# FLEXQCMV1_4.net
KiCad netlist of a schematic drawn in EAGLE
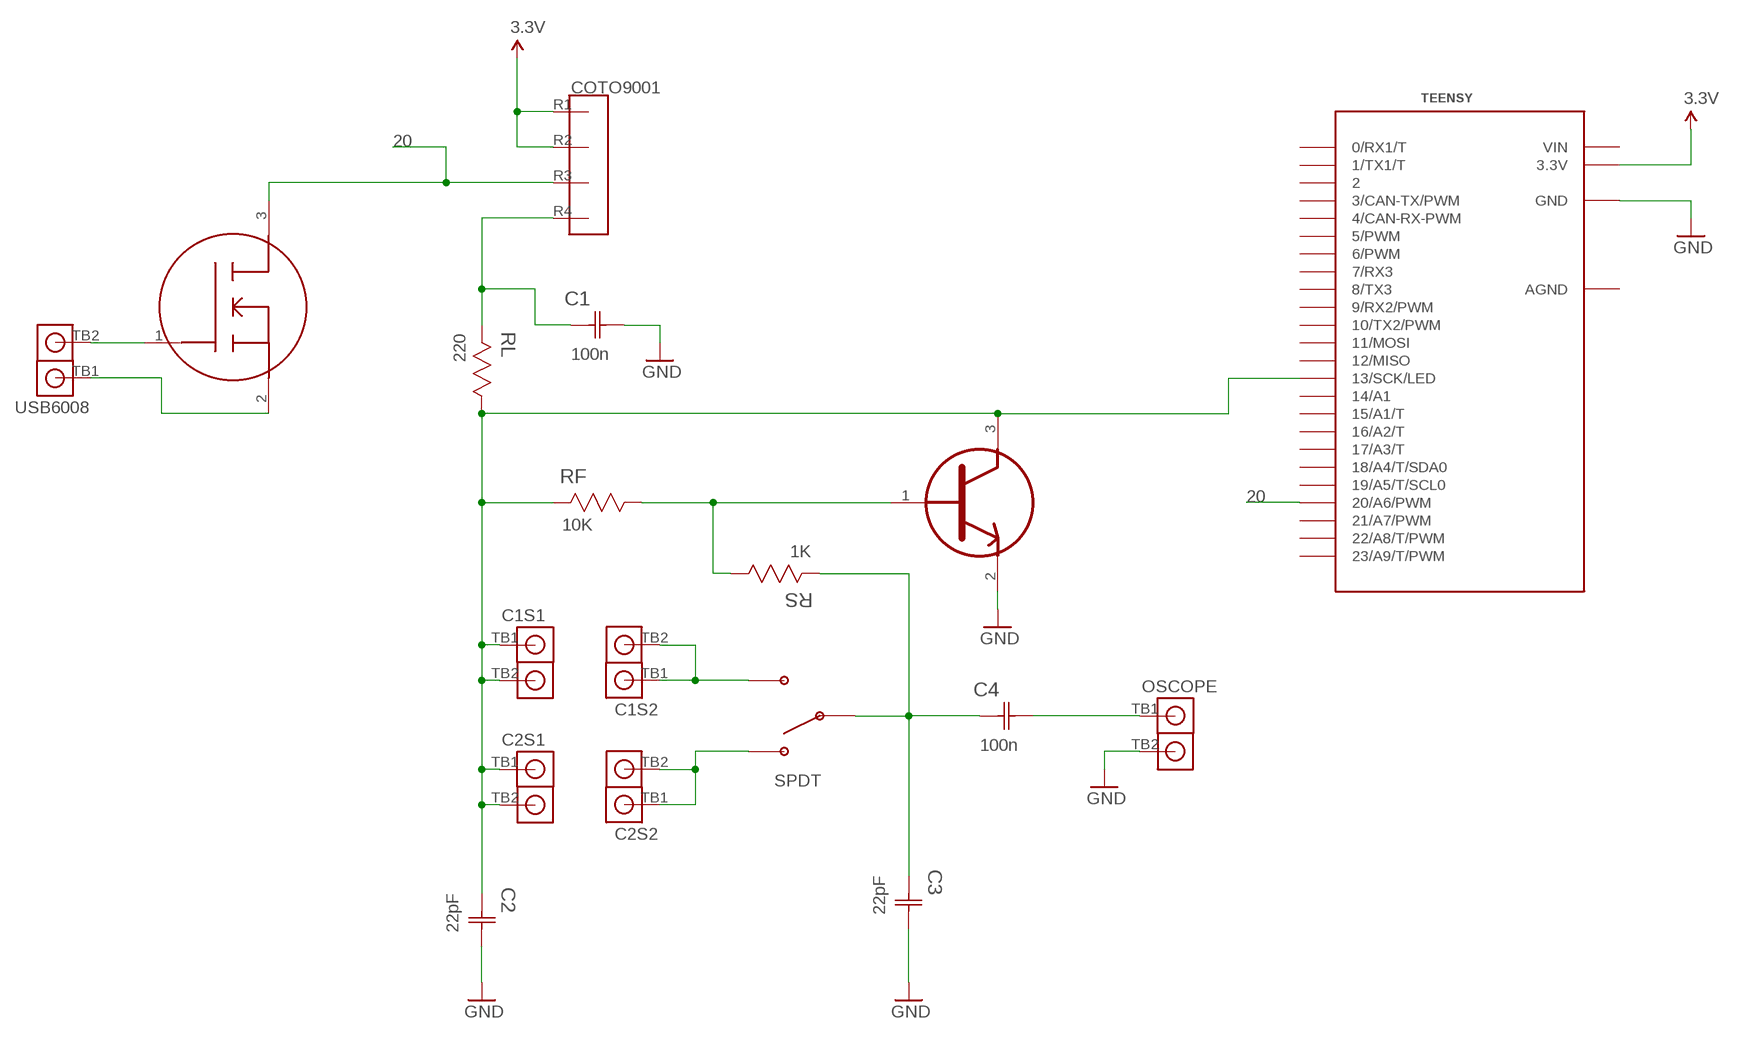
[diagram p0: schematic, sheet 1]

(export (version "E")
  (design (tool "Eeschema 10.0.6"))
  (components
    (comp (ref "C1")
      (value "100n")
      (footprint "eagle-import:CAPC3216X88N")
      (fields (field (name "MPN") "C1206C104K1RACTU") (field (name "TOLERANCE") "±10%"))
      (libsource (lib "eagle-import") (part "C1206C104K1RACTU"))
    )
    (comp (ref "C1S1")
      (value "TERMBLOCKX2")
      (footprint "eagle-import:TERMBLOCKX2")
      (libsource (lib "eagle-import") (part "TERMBLOCKX2"))
    )
    (comp (ref "C1S2")
      (value "TERMBLOCKX2")
      (footprint "eagle-import:TERMBLOCKX2")
      (libsource (lib "eagle-import") (part "TERMBLOCKX2"))
    )
    (comp (ref "C2")
      (value "22pF")
      (footprint "eagle-import:CAPC3216X88N")
      (fields (field (name "MPN") "C1206C220J5GACTU") (field (name "TOLERANCE") "±5%"))
      (libsource (lib "eagle-import") (part "C1206C220J5GACTU"))
    )
    (comp (ref "C2S1")
      (value "TERMBLOCKX2")
      (footprint "eagle-import:TERMBLOCKX2")
      (libsource (lib "eagle-import") (part "TERMBLOCKX2"))
    )
    (comp (ref "C2S2")
      (value "TERMBLOCKX2")
      (footprint "eagle-import:TERMBLOCKX2")
      (libsource (lib "eagle-import") (part "TERMBLOCKX2"))
    )
    (comp (ref "C3")
      (value "22pF")
      (footprint "eagle-import:CAPC3216X88N")
      (fields (field (name "MPN") "C1206C220J5GACTU") (field (name "TOLERANCE") "±5%"))
      (libsource (lib "eagle-import") (part "C1206C220J5GACTU"))
    )
    (comp (ref "C4")
      (value "100n")
      (footprint "eagle-import:CAPC3216X88N")
      (fields (field (name "MPN") "C1206C104K1RACTU") (field (name "TOLERANCE") "±10%"))
      (libsource (lib "eagle-import") (part "C1206C104K1RACTU"))
    )
    (comp (ref "COTO9001")
      (value "COTO9001")
      (footprint "eagle-import:COTO9001")
      (libsource (lib "eagle-import") (part "COTO9001"))
    )
    (comp (ref "OSCOPE")
      (value "TERMBLOCKX2")
      (footprint "eagle-import:TERMBLOCKX2")
      (libsource (lib "eagle-import") (part "TERMBLOCKX2"))
    )
    (comp (ref "RF")
      (value "10K")
      (footprint "eagle-import:RESC3216X71N")
      (fields (field (name "MPN") "CRCW120610K0FKEA") (field (name "TOLERANCE") "±1%"))
      (libsource (lib "eagle-import") (part "CRCW120610K0FKEA"))
    )
    (comp (ref "RL")
      (value "220")
      (footprint "eagle-import:RESC3216X71N")
      (fields (field (name "MPN") "CRCW1206220RJNEA") (field (name "TOLERANCE") "±5%"))
      (libsource (lib "eagle-import") (part "CRCW1206220RJNEA"))
    )
    (comp (ref "RS")
      (value "1K")
      (footprint "eagle-import:RESC3216X71N")
      (fields (field (name "MPN") "CRCW12061K00FKEA") (field (name "TOLERANCE") "±1%"))
      (libsource (lib "eagle-import") (part "CRCW12061K00FKEA"))
    )
    (comp (ref "SPDT")
      (value "SPDTSWITCH")
      (footprint "eagle-import:SPDTSWITCH")
      (libsource (lib "eagle-import") (part "SPDTSWITCH"))
    )
    (comp (ref "TEENSY")
      (value "TEENSY_3.1_DIL")
      (footprint "eagle-import:TEENSY3-DIL")
      (libsource (lib "eagle-import") (part "TEENSY_3.1_DIL"))
    )
    (comp (ref "U1")
      (value "FET")
      (footprint "eagle-import:SOT95P230X110-3N")
      (fields (field (name "MPN") "2N7002K"))
      (libsource (lib "eagle-import") (part "2N7002K"))
    )
    (comp (ref "U2")
      (value "BJT")
      (footprint "eagle-import:SOT95P230X110-3N")
      (libsource (lib "eagle-import") (part "BC847C"))
    )
    (comp (ref "USB6008")
      (value "TERMBLOCKX2")
      (footprint "eagle-import:TERMBLOCKX2")
      (libsource (lib "eagle-import") (part "TERMBLOCKX2"))
    )
  )
  (nets
    (net (code "1") (name "/20") (class "Default")
      (node (ref "COTO9001") (pin "R3") (pinfunction "R3_R3") (pintype "bidirectional"))
      (node (ref "TEENSY") (pin "20/A6") (pinfunction "20/A6/PWM_20/A6") (pintype "bidirectional"))
      (node (ref "U1") (pin "3") (pinfunction "D_3") (pintype "bidirectional"))
    )
    (net (code "2") (name "/AGND") (class "Default")
      (node (ref "TEENSY") (pin "AGND") (pinfunction "AGND_AGND") (pintype "power_in"))
    )
    (net (code "3") (name "/VIN") (class "Default")
      (node (ref "TEENSY") (pin "VIN") (pinfunction "VIN_VIN") (pintype "power_in"))
    )
    (net (code "4") (name "3.3V") (class "Default")
      (node (ref "COTO9001") (pin "R1") (pinfunction "R1_R1") (pintype "bidirectional"))
      (node (ref "COTO9001") (pin "R2") (pinfunction "R2_R2") (pintype "bidirectional"))
      (node (ref "TEENSY") (pin "3.3V") (pinfunction "3.3V_3.3V") (pintype "power_in"))
    )
    (net (code "5") (name "GND") (class "Default")
      (node (ref "C1") (pin "2") (pinfunction "C2_2") (pintype "passive"))
      (node (ref "C2") (pin "2") (pinfunction "C2_2") (pintype "passive"))
      (node (ref "C3") (pin "2") (pinfunction "C2_2") (pintype "passive"))
      (node (ref "OSCOPE") (pin "TB2") (pinfunction "TB2_TB2") (pintype "bidirectional"))
      (node (ref "TEENSY") (pin "GND") (pinfunction "GND_GND") (pintype "power_in"))
      (node (ref "U2") (pin "2") (pinfunction "E_2") (pintype "bidirectional"))
    )
    (net (code "6") (name "Net-(C1-C1)") (class "Default")
      (node (ref "C1") (pin "1") (pinfunction "C1_1") (pintype "passive"))
      (node (ref "COTO9001") (pin "R4") (pinfunction "R4_R4") (pintype "bidirectional"))
      (node (ref "RL") (pin "2") (pinfunction "2_2") (pintype "passive"))
    )
    (net (code "7") (name "Net-(C1S2-PadTB1)") (class "Default")
      (node (ref "C1S2") (pin "TB1") (pinfunction "TB1_TB1") (pintype "bidirectional"))
      (node (ref "C1S2") (pin "TB2") (pinfunction "TB2_TB2") (pintype "bidirectional"))
      (node (ref "SPDT") (pin "SW3") (pinfunction "SW3_SW3") (pintype "bidirectional"))
    )
    (net (code "8") (name "Net-(C2-C1)") (class "Default")
      (node (ref "C1S1") (pin "TB1") (pinfunction "TB1_TB1") (pintype "bidirectional"))
      (node (ref "C1S1") (pin "TB2") (pinfunction "TB2_TB2") (pintype "bidirectional"))
      (node (ref "C2") (pin "1") (pinfunction "C1_1") (pintype "passive"))
      (node (ref "C2S1") (pin "TB1") (pinfunction "TB1_TB1") (pintype "bidirectional"))
      (node (ref "C2S1") (pin "TB2") (pinfunction "TB2_TB2") (pintype "bidirectional"))
      (node (ref "RF") (pin "2") (pinfunction "2_2") (pintype "passive"))
      (node (ref "RL") (pin "1") (pinfunction "1_1") (pintype "passive"))
      (node (ref "TEENSY") (pin "13") (pinfunction "13/SCK/LED_13") (pintype "bidirectional"))
      (node (ref "U2") (pin "3") (pinfunction "C_3") (pintype "bidirectional"))
    )
    (net (code "9") (name "Net-(C2S2-PadTB1)") (class "Default")
      (node (ref "C2S2") (pin "TB1") (pinfunction "TB1_TB1") (pintype "bidirectional"))
      (node (ref "C2S2") (pin "TB2") (pinfunction "TB2_TB2") (pintype "bidirectional"))
      (node (ref "SPDT") (pin "SW1") (pinfunction "SW1_SW1") (pintype "bidirectional"))
    )
    (net (code "10") (name "Net-(C3-C1)") (class "Default")
      (node (ref "C3") (pin "1") (pinfunction "C1_1") (pintype "passive"))
      (node (ref "C4") (pin "1") (pinfunction "C1_1") (pintype "passive"))
      (node (ref "RS") (pin "2") (pinfunction "2_2") (pintype "passive"))
      (node (ref "SPDT") (pin "SW2") (pinfunction "SW2_SW2") (pintype "bidirectional"))
    )
    (net (code "11") (name "Net-(C4-C2)") (class "Default")
      (node (ref "C4") (pin "2") (pinfunction "C2_2") (pintype "passive"))
      (node (ref "OSCOPE") (pin "TB1") (pinfunction "TB1_TB1") (pintype "bidirectional"))
    )
    (net (code "12") (name "Net-(U1-G)") (class "Default")
      (node (ref "U1") (pin "1") (pinfunction "G_1") (pintype "bidirectional"))
      (node (ref "USB6008") (pin "TB2") (pinfunction "TB2_TB2") (pintype "bidirectional"))
    )
    (net (code "13") (name "Net-(U1-S)") (class "Default")
      (node (ref "U1") (pin "2") (pinfunction "S_2") (pintype "bidirectional"))
      (node (ref "USB6008") (pin "TB1") (pinfunction "TB1_TB1") (pintype "bidirectional"))
    )
    (net (code "14") (name "Net-(U2-B)") (class "Default")
      (node (ref "RF") (pin "1") (pinfunction "1_1") (pintype "passive"))
      (node (ref "RS") (pin "1") (pinfunction "1_1") (pintype "passive"))
      (node (ref "U2") (pin "1") (pinfunction "B_1") (pintype "bidirectional"))
    )
    (net (code "15") (name "unconnected-(TEENSY-0{slash}RX1{slash}T-Pad0)") (class "Default")
      (node (ref "TEENSY") (pin "0") (pinfunction "0/RX1/T_0") (pintype "bidirectional"))
    )
    (net (code "16") (name "unconnected-(TEENSY-1{slash}TX1{slash}T-Pad1)") (class "Default")
      (node (ref "TEENSY") (pin "1") (pinfunction "1/TX1/T_1") (pintype "bidirectional"))
    )
    (net (code "17") (name "unconnected-(TEENSY-3{slash}CAN-TX{slash}PWM-Pad3)") (class "Default")
      (node (ref "TEENSY") (pin "3") (pinfunction "3/CAN-TX/PWM_3") (pintype "bidirectional"))
    )
    (net (code "18") (name "unconnected-(TEENSY-4{slash}CAN-RX-PWM-Pad4)") (class "Default")
      (node (ref "TEENSY") (pin "4") (pinfunction "4/CAN-RX-PWM_4") (pintype "bidirectional"))
    )
    (net (code "19") (name "unconnected-(TEENSY-5{slash}PWM-Pad5)") (class "Default")
      (node (ref "TEENSY") (pin "5") (pinfunction "5/PWM_5") (pintype "bidirectional"))
    )
    (net (code "20") (name "unconnected-(TEENSY-6{slash}PWM-Pad6)") (class "Default")
      (node (ref "TEENSY") (pin "6") (pinfunction "6/PWM_6") (pintype "bidirectional"))
    )
    (net (code "21") (name "unconnected-(TEENSY-7{slash}RX3-Pad7)") (class "Default")
      (node (ref "TEENSY") (pin "7") (pinfunction "7/RX3_7") (pintype "bidirectional"))
    )
    (net (code "22") (name "unconnected-(TEENSY-8{slash}TX3-Pad8)") (class "Default")
      (node (ref "TEENSY") (pin "8") (pinfunction "8/TX3_8") (pintype "bidirectional"))
    )
    (net (code "23") (name "unconnected-(TEENSY-9{slash}RX2{slash}PWM-Pad9)") (class "Default")
      (node (ref "TEENSY") (pin "9") (pinfunction "9/RX2/PWM_9") (pintype "bidirectional"))
    )
    (net (code "24") (name "unconnected-(TEENSY-10{slash}TX2{slash}PWM-Pad10)") (class "Default")
      (node (ref "TEENSY") (pin "10") (pinfunction "10/TX2/PWM_10") (pintype "bidirectional"))
    )
    (net (code "25") (name "unconnected-(TEENSY-11{slash}MOSI-Pad11)") (class "Default")
      (node (ref "TEENSY") (pin "11") (pinfunction "11/MOSI_11") (pintype "bidirectional"))
    )
    (net (code "26") (name "unconnected-(TEENSY-12{slash}MISO-Pad12)") (class "Default")
      (node (ref "TEENSY") (pin "12") (pinfunction "12/MISO_12") (pintype "bidirectional"))
    )
    (net (code "27") (name "unconnected-(TEENSY-14{slash}A1-Pad14{slash}A0)") (class "Default")
      (node (ref "TEENSY") (pin "14/A0") (pinfunction "14/A1_14/A0") (pintype "bidirectional"))
    )
    (net (code "28") (name "unconnected-(TEENSY-15{slash}A1{slash}T-Pad15{slash}A1)") (class "Default")
      (node (ref "TEENSY") (pin "15/A1") (pinfunction "15/A1/T_15/A1") (pintype "bidirectional"))
    )
    (net (code "29") (name "unconnected-(TEENSY-16{slash}A2{slash}T-Pad16{slash}A2)") (class "Default")
      (node (ref "TEENSY") (pin "16/A2") (pinfunction "16/A2/T_16/A2") (pintype "bidirectional"))
    )
    (net (code "30") (name "unconnected-(TEENSY-17{slash}A3{slash}T-Pad17{slash}A3)") (class "Default")
      (node (ref "TEENSY") (pin "17/A3") (pinfunction "17/A3/T_17/A3") (pintype "bidirectional"))
    )
    (net (code "31") (name "unconnected-(TEENSY-18{slash}A4{slash}T{slash}SDA0-Pad18{slash}A4)") (class "Default")
      (node (ref "TEENSY") (pin "18/A4") (pinfunction "18/A4/T/SDA0_18/A4") (pintype "bidirectional"))
    )
    (net (code "32") (name "unconnected-(TEENSY-19{slash}A5{slash}T{slash}SCL0-Pad19{slash}A5)") (class "Default")
      (node (ref "TEENSY") (pin "19/A5") (pinfunction "19/A5/T/SCL0_19/A5") (pintype "bidirectional"))
    )
    (net (code "33") (name "unconnected-(TEENSY-21{slash}A7{slash}PWM-Pad21{slash}A7)") (class "Default")
      (node (ref "TEENSY") (pin "21/A7") (pinfunction "21/A7/PWM_21/A7") (pintype "bidirectional"))
    )
    (net (code "34") (name "unconnected-(TEENSY-22{slash}A8{slash}T{slash}PWM-Pad22{slash}A8)") (class "Default")
      (node (ref "TEENSY") (pin "22/A8") (pinfunction "22/A8/T/PWM_22/A8") (pintype "bidirectional"))
    )
    (net (code "35") (name "unconnected-(TEENSY-23{slash}A9{slash}T{slash}PWM-Pad23{slash}A9)") (class "Default")
      (node (ref "TEENSY") (pin "23/A9") (pinfunction "23/A9/T/PWM_23/A9") (pintype "bidirectional"))
    )
    (net (code "36") (name "unconnected-(TEENSY-Pad2)") (class "Default")
      (node (ref "TEENSY") (pin "2") (pinfunction "2_2") (pintype "bidirectional"))
    )
  )
)
